# PlantDuino_v2_0.net
KiCad netlist of a schematic drawn in EAGLE
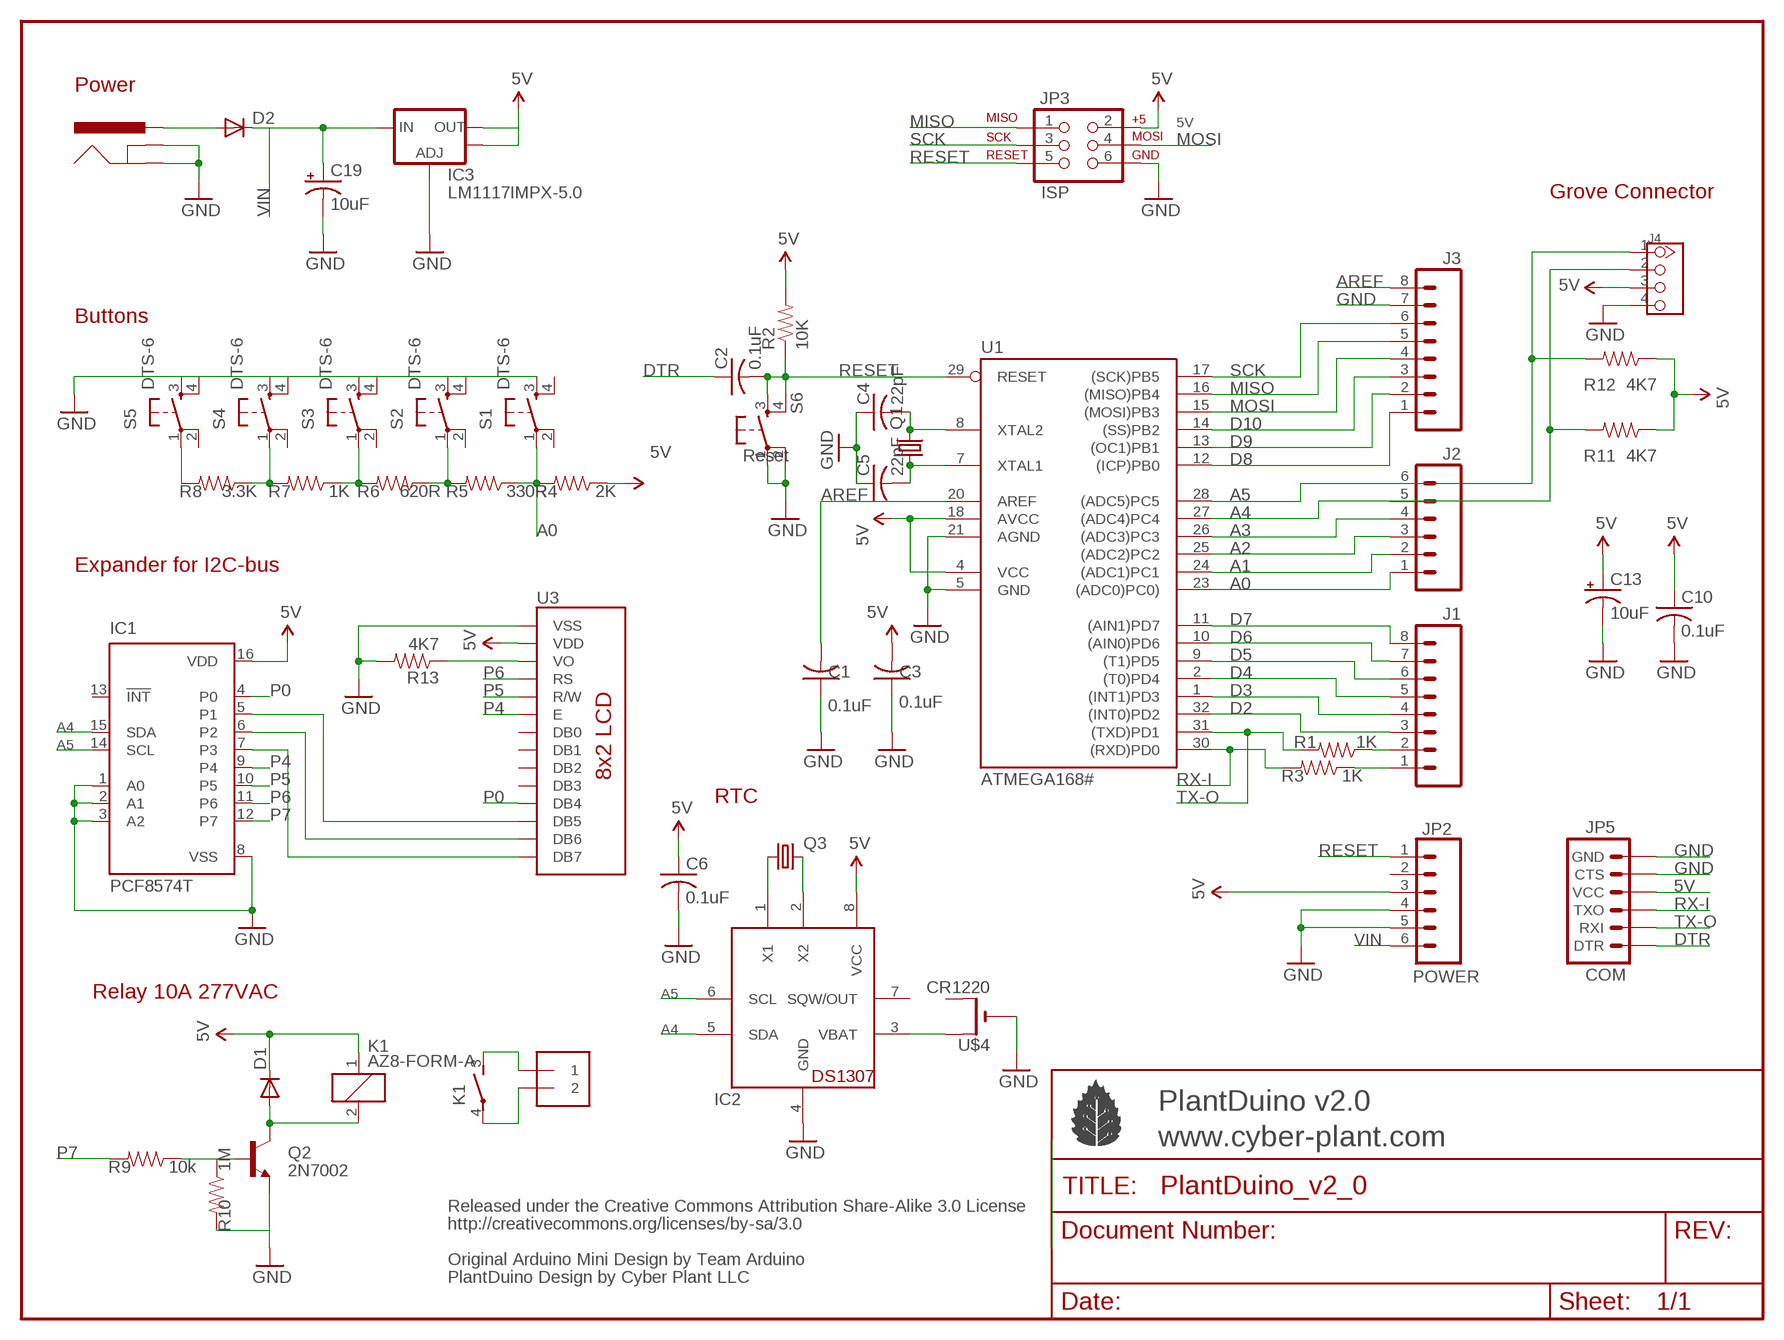
[diagram p0: schematic, sheet 1]

(export (version "E")
  (design (tool "Eeschema 10.0.6"))
  (components
    (comp (ref "C1")
      (value "0.1uF")
      (footprint "eagle-import:C1206")
      (libsource (lib "eagle-import") (part "C-USC1206"))
    )
    (comp (ref "C2")
      (value "0.1uF")
      (footprint "eagle-import:C1206")
      (libsource (lib "eagle-import") (part "C-USC1206"))
    )
    (comp (ref "C3")
      (value "0.1uF")
      (footprint "eagle-import:C1206")
      (libsource (lib "eagle-import") (part "C-USC1206"))
    )
    (comp (ref "C4")
      (value "22pF")
      (footprint "eagle-import:C1206")
      (libsource (lib "eagle-import") (part "C-USC1206"))
    )
    (comp (ref "C5")
      (value "22pF")
      (footprint "eagle-import:C1206")
      (libsource (lib "eagle-import") (part "C-USC1206"))
    )
    (comp (ref "C6")
      (value "0.1uF")
      (footprint "eagle-import:C1206")
      (libsource (lib "eagle-import") (part "C-USC1206"))
    )
    (comp (ref "C10")
      (value "0.1uF")
      (footprint "eagle-import:C1206")
      (libsource (lib "eagle-import") (part "C-USC1206"))
    )
    (comp (ref "C13")
      (value "10uF")
      (footprint "eagle-import:EIA6032")
      (libsource (lib "eagle-import") (part "CAP_POL6032"))
    )
    (comp (ref "C19")
      (value "10uF")
      (footprint "eagle-import:EIA6032")
      (libsource (lib "eagle-import") (part "CAP_POL6032"))
    )
    (comp (ref "D1")
      (value "DIODESMA")
      (footprint "eagle-import:SMA-DIODE")
      (libsource (lib "eagle-import") (part "DIODESMA"))
    )
    (comp (ref "D2")
      (value "DIODESMA")
      (footprint "eagle-import:SMA-DIODE")
      (libsource (lib "eagle-import") (part "DIODESMA"))
    )
    (comp (ref "IC1")
      (value "PCF8574T")
      (footprint "eagle-import:SO16W")
      (fields (field (name "MPN") "PCF8574T/3,512"))
      (libsource (lib "eagle-import") (part "PCF8574T"))
    )
    (comp (ref "IC2")
      (value "DS1307")
      (footprint "eagle-import:SO08")
      (libsource (lib "eagle-import") (part "DS1307"))
    )
    (comp (ref "IC3")
      (value "LM1117IMPX-5.0")
      (footprint "eagle-import:SOT223")
      (libsource (lib "eagle-import") (part "V_REG_LM1117SOT223"))
    )
    (comp (ref "J1")
      (value "M08LONGPADS")
      (footprint "eagle-import:1X08_LONGPADS")
      (libsource (lib "eagle-import") (part "M08LONGPADS"))
    )
    (comp (ref "J2")
      (value "M06LONGPADS")
      (footprint "eagle-import:1X06_LONGPADS")
      (libsource (lib "eagle-import") (part "M06LONGPADS"))
    )
    (comp (ref "J3")
      (value "M08LONGPADS")
      (footprint "eagle-import:1X08_LONGPADS")
      (libsource (lib "eagle-import") (part "M08LONGPADS"))
    )
    (comp (ref "J4")
      (value "TWIG-4P-2.090D")
      (footprint "eagle-import:4P-2.0-90D")
      (libsource (lib "eagle-import") (part "TWIG-4P-2.090D"))
    )
    (comp (ref "JP1")
      (value "1X2-3.5MM")
      (footprint "eagle-import:1X2-3.5MM")
      (libsource (lib "eagle-import") (part "1X2-3.5MM"))
    )
    (comp (ref "JP2")
      (value "POWER")
      (footprint "eagle-import:1X06_LONGPADS")
      (libsource (lib "eagle-import") (part "M06LONGPADS"))
    )
    (comp (ref "JP3")
      (value "ISP")
      (footprint "eagle-import:2X3")
      (libsource (lib "eagle-import") (part "AVR_SPI_PRG_6PTH"))
    )
    (comp (ref "JP4")
      (value "Power Jack")
      (footprint "eagle-import:POWER_JACK_PTH")
      (libsource (lib "eagle-import") (part "POWER_JACKPTH"))
    )
    (comp (ref "JP5")
      (value "COM")
      (footprint "eagle-import:1X06")
      (libsource (lib "eagle-import") (part "ARDUINO_SERIAL_PROGRAMPTH"))
    )
    (comp (ref "K1")
      (value "AZ8-FORM-A")
      (footprint "eagle-import:AZ8")
      (libsource (lib "eagle-import") (part "AZ8-FORM-A"))
    )
    (comp (ref "Q1")
      (value "CRYTALHC49S")
      (footprint "eagle-import:HC49_S@1")
      (libsource (lib "eagle-import") (part "CRYTALHC49S"))
    )
    (comp (ref "Q2")
      (value "2N7002")
      (footprint "eagle-import:SOT23")
      (libsource (lib "eagle-import") (part "TRANSISTOR_NPNSOT23"))
    )
    (comp (ref "Q3")
      (value "CRYSTALTC26H")
      (footprint "eagle-import:TC26H")
      (libsource (lib "eagle-import") (part "CRYSTALTC26H"))
    )
    (comp (ref "R1")
      (value "1K")
      (footprint "eagle-import:1206")
      (libsource (lib "eagle-import") (part "RESISTOR1206"))
    )
    (comp (ref "R2")
      (value "10K")
      (footprint "eagle-import:1206")
      (libsource (lib "eagle-import") (part "RESISTOR1206"))
    )
    (comp (ref "R3")
      (value "1K")
      (footprint "eagle-import:1206")
      (libsource (lib "eagle-import") (part "RESISTOR1206"))
    )
    (comp (ref "R4")
      (value "2K")
      (footprint "eagle-import:1206")
      (libsource (lib "eagle-import") (part "RESISTOR1206"))
    )
    (comp (ref "R5")
      (value "330R")
      (footprint "eagle-import:1206")
      (libsource (lib "eagle-import") (part "RESISTOR1206"))
    )
    (comp (ref "R6")
      (value "620R")
      (footprint "eagle-import:1206")
      (libsource (lib "eagle-import") (part "RESISTOR1206"))
    )
    (comp (ref "R7")
      (value "1K")
      (footprint "eagle-import:1206")
      (libsource (lib "eagle-import") (part "RESISTOR1206"))
    )
    (comp (ref "R8")
      (value "3.3K")
      (footprint "eagle-import:1206")
      (libsource (lib "eagle-import") (part "RESISTOR1206"))
    )
    (comp (ref "R9")
      (value "10k")
      (footprint "eagle-import:1206")
      (libsource (lib "eagle-import") (part "RESISTOR1206"))
    )
    (comp (ref "R10")
      (value "1M")
      (footprint "eagle-import:1206")
      (libsource (lib "eagle-import") (part "RESISTOR1206"))
    )
    (comp (ref "R11")
      (value "4K7")
      (footprint "eagle-import:1206")
      (libsource (lib "eagle-import") (part "RESISTOR1206"))
    )
    (comp (ref "R12")
      (value "4K7")
      (footprint "eagle-import:1206")
      (libsource (lib "eagle-import") (part "RESISTOR1206"))
    )
    (comp (ref "R13")
      (value "4K7")
      (footprint "eagle-import:1206")
      (libsource (lib "eagle-import") (part "RESISTOR1206"))
    )
    (comp (ref "S1")
      (value "DTS-6")
      (footprint "eagle-import:DTS-6")
      (libsource (lib "eagle-import") (part "DTS-6"))
    )
    (comp (ref "S2")
      (value "DTS-6")
      (footprint "eagle-import:DTS-6")
      (libsource (lib "eagle-import") (part "DTS-6"))
    )
    (comp (ref "S3")
      (value "DTS-6")
      (footprint "eagle-import:DTS-6")
      (libsource (lib "eagle-import") (part "DTS-6"))
    )
    (comp (ref "S4")
      (value "DTS-6")
      (footprint "eagle-import:DTS-6")
      (libsource (lib "eagle-import") (part "DTS-6"))
    )
    (comp (ref "S5")
      (value "DTS-6")
      (footprint "eagle-import:DTS-6")
      (libsource (lib "eagle-import") (part "DTS-6"))
    )
    (comp (ref "S6")
      (value "Reset")
      (footprint "eagle-import:DTS-6")
      (libsource (lib "eagle-import") (part "DTS-6"))
    )
    (comp (ref "U$4")
      (value "CR1220")
      (footprint "eagle-import:CR1220-THM")
      (libsource (lib "eagle-import") (part "CR1220THM"))
    )
    (comp (ref "U1")
      (value "ATMEGA168#")
      (footprint "eagle-import:TQFP32-08")
      (libsource (lib "eagle-import") (part "AT90S4433A"))
    )
    (comp (ref "U3")
      (value "LCD-8X2-WH0802A8X2")
      (footprint "eagle-import:LCD-8X2-WH0802A")
      (libsource (lib "eagle-import") (part "LCD-8X2-WH0802A8X2"))
    )
  )
  (nets
    (net (code "1") (name "/A0") (class "Default")
      (node (ref "J2") (pin "1") (pinfunction "1_1") (pintype "passive"))
      (node (ref "R4") (pin "2") (pinfunction "2_2") (pintype "passive"))
      (node (ref "R5") (pin "1") (pinfunction "1_1") (pintype "passive"))
      (node (ref "S1") (pin "1") (pinfunction "1_1") (pintype "passive"))
      (node (ref "U1") (pin "23") (pinfunction "(ADC0)PC0)_23") (pintype "bidirectional"))
    )
    (net (code "2") (name "/A1") (class "Default")
      (node (ref "J2") (pin "2") (pinfunction "2_2") (pintype "passive"))
      (node (ref "U1") (pin "24") (pinfunction "(ADC1)PC1_24") (pintype "bidirectional"))
    )
    (net (code "3") (name "/A2") (class "Default")
      (node (ref "J2") (pin "3") (pinfunction "3_3") (pintype "passive"))
      (node (ref "U1") (pin "25") (pinfunction "(ADC2)PC2_25") (pintype "bidirectional"))
    )
    (net (code "4") (name "/A3") (class "Default")
      (node (ref "J2") (pin "4") (pinfunction "4_4") (pintype "passive"))
      (node (ref "U1") (pin "26") (pinfunction "(ADC3)PC3_26") (pintype "bidirectional"))
    )
    (net (code "5") (name "/A4") (class "Default")
      (node (ref "IC1") (pin "15") (pinfunction "SDA_15") (pintype "bidirectional"))
      (node (ref "IC2") (pin "5") (pinfunction "SDA_5") (pintype "bidirectional"))
      (node (ref "J2") (pin "5") (pinfunction "5_5") (pintype "passive"))
      (node (ref "J4") (pin "2") (pinfunction "2_2") (pintype "bidirectional"))
      (node (ref "R11") (pin "2") (pinfunction "2_2") (pintype "passive"))
      (node (ref "U1") (pin "27") (pinfunction "(ADC4)PC4_27") (pintype "bidirectional"))
    )
    (net (code "6") (name "/A5") (class "Default")
      (node (ref "IC1") (pin "14") (pinfunction "SCL_14") (pintype "input"))
      (node (ref "IC2") (pin "6") (pinfunction "SCL_6") (pintype "bidirectional"))
      (node (ref "J2") (pin "6") (pinfunction "6_6") (pintype "passive"))
      (node (ref "J4") (pin "1") (pinfunction "1_1") (pintype "bidirectional"))
      (node (ref "R12") (pin "2") (pinfunction "2_2") (pintype "passive"))
      (node (ref "U1") (pin "28") (pinfunction "(ADC5)PC5_28") (pintype "bidirectional"))
    )
    (net (code "7") (name "/AREF") (class "Default")
      (node (ref "C1") (pin "2") (pinfunction "2_2") (pintype "passive"))
      (node (ref "J3") (pin "8") (pinfunction "8_8") (pintype "passive"))
      (node (ref "U1") (pin "20") (pinfunction "AREF_20") (pintype "power_in"))
    )
    (net (code "8") (name "/D2") (class "Default")
      (node (ref "J1") (pin "3") (pinfunction "3_3") (pintype "passive"))
      (node (ref "U1") (pin "32") (pinfunction "(INT0)PD2_32") (pintype "bidirectional"))
    )
    (net (code "9") (name "/D3") (class "Default")
      (node (ref "J1") (pin "4") (pinfunction "4_4") (pintype "passive"))
      (node (ref "U1") (pin "1") (pinfunction "(INT1)PD3_1") (pintype "bidirectional"))
    )
    (net (code "10") (name "/D4") (class "Default")
      (node (ref "J1") (pin "5") (pinfunction "5_5") (pintype "passive"))
      (node (ref "U1") (pin "2") (pinfunction "(T0)PD4_2") (pintype "bidirectional"))
    )
    (net (code "11") (name "/D5") (class "Default")
      (node (ref "J1") (pin "6") (pinfunction "6_6") (pintype "passive"))
      (node (ref "U1") (pin "9") (pinfunction "(T1)PD5_9") (pintype "bidirectional"))
    )
    (net (code "12") (name "/D6") (class "Default")
      (node (ref "J1") (pin "7") (pinfunction "7_7") (pintype "passive"))
      (node (ref "U1") (pin "10") (pinfunction "(AIN0)PD6_10") (pintype "bidirectional"))
    )
    (net (code "13") (name "/D7") (class "Default")
      (node (ref "J1") (pin "8") (pinfunction "8_8") (pintype "passive"))
      (node (ref "U1") (pin "11") (pinfunction "(AIN1)PD7_11") (pintype "bidirectional"))
    )
    (net (code "14") (name "/D8") (class "Default")
      (node (ref "J3") (pin "1") (pinfunction "1_1") (pintype "passive"))
      (node (ref "U1") (pin "12") (pinfunction "(ICP)PB0_12") (pintype "bidirectional"))
    )
    (net (code "15") (name "/D9") (class "Default")
      (node (ref "J3") (pin "2") (pinfunction "2_2") (pintype "passive"))
      (node (ref "U1") (pin "13") (pinfunction "(OC1)PB1_13") (pintype "bidirectional"))
    )
    (net (code "16") (name "/D10") (class "Default")
      (node (ref "J3") (pin "3") (pinfunction "3_3") (pintype "passive"))
      (node (ref "U1") (pin "14") (pinfunction "(SS)PB2_14") (pintype "bidirectional"))
    )
    (net (code "17") (name "/DTR") (class "Default")
      (node (ref "C2") (pin "1") (pinfunction "1_1") (pintype "passive"))
      (node (ref "JP5") (pin "1") (pinfunction "DTR_1") (pintype "passive"))
    )
    (net (code "18") (name "/MISO") (class "Default")
      (node (ref "J3") (pin "5") (pinfunction "5_5") (pintype "passive"))
      (node (ref "JP3") (pin "1") (pinfunction "1_1") (pintype "passive"))
      (node (ref "U1") (pin "16") (pinfunction "(MISO)PB4_16") (pintype "bidirectional"))
    )
    (net (code "19") (name "/MOSI") (class "Default")
      (node (ref "J3") (pin "4") (pinfunction "4_4") (pintype "passive"))
      (node (ref "JP3") (pin "4") (pinfunction "4_4") (pintype "passive"))
      (node (ref "U1") (pin "15") (pinfunction "(MOSI)PB3_15") (pintype "bidirectional"))
    )
    (net (code "20") (name "/P0") (class "Default")
      (node (ref "IC1") (pin "4") (pinfunction "P0_4") (pintype "bidirectional"))
      (node (ref "U3") (pin "11") (pinfunction "DB4_11") (pintype "bidirectional"))
    )
    (net (code "21") (name "/P4") (class "Default")
      (node (ref "IC1") (pin "9") (pinfunction "P4_9") (pintype "bidirectional"))
      (node (ref "U3") (pin "6") (pinfunction "E_6") (pintype "input"))
    )
    (net (code "22") (name "/P5") (class "Default")
      (node (ref "IC1") (pin "10") (pinfunction "P5_10") (pintype "bidirectional"))
      (node (ref "U3") (pin "5") (pinfunction "R/W_5") (pintype "input"))
    )
    (net (code "23") (name "/P6") (class "Default")
      (node (ref "IC1") (pin "11") (pinfunction "P6_11") (pintype "bidirectional"))
      (node (ref "U3") (pin "4") (pinfunction "RS_4") (pintype "input"))
    )
    (net (code "24") (name "/P7") (class "Default")
      (node (ref "IC1") (pin "12") (pinfunction "P7_12") (pintype "bidirectional"))
      (node (ref "R9") (pin "2") (pinfunction "2_2") (pintype "passive"))
    )
    (net (code "25") (name "/RESET") (class "Default")
      (node (ref "C2") (pin "2") (pinfunction "2_2") (pintype "passive"))
      (node (ref "JP2") (pin "1") (pinfunction "1_1") (pintype "passive"))
      (node (ref "JP3") (pin "5") (pinfunction "5_5") (pintype "passive"))
      (node (ref "R2") (pin "1") (pinfunction "1_1") (pintype "passive"))
      (node (ref "S6") (pin "3") (pinfunction "3_3") (pintype "passive"))
      (node (ref "S6") (pin "4") (pinfunction "4_4") (pintype "passive"))
      (node (ref "U1") (pin "29") (pinfunction "RESET_29") (pintype "input"))
    )
    (net (code "26") (name "/RX-I") (class "Default")
      (node (ref "JP5") (pin "3") (pinfunction "TXO_3") (pintype "passive"))
      (node (ref "R3") (pin "2") (pinfunction "2_2") (pintype "passive"))
      (node (ref "U1") (pin "30") (pinfunction "(RXD)PD0_30") (pintype "bidirectional"))
    )
    (net (code "27") (name "/SCK") (class "Default")
      (node (ref "J3") (pin "6") (pinfunction "6_6") (pintype "passive"))
      (node (ref "JP3") (pin "3") (pinfunction "3_3") (pintype "passive"))
      (node (ref "U1") (pin "17") (pinfunction "(SCK)PB5_17") (pintype "bidirectional"))
    )
    (net (code "28") (name "/TX-O") (class "Default")
      (node (ref "JP5") (pin "2") (pinfunction "RXI_2") (pintype "passive"))
      (node (ref "R1") (pin "2") (pinfunction "2_2") (pintype "passive"))
      (node (ref "U1") (pin "31") (pinfunction "(TXD)PD1_31") (pintype "bidirectional"))
    )
    (net (code "29") (name "/VIN") (class "Default")
      (node (ref "C19") (pin "P$1") (pinfunction "+_P$1") (pintype "passive"))
      (node (ref "D2") (pin "C") (pinfunction "C_C") (pintype "passive"))
      (node (ref "IC3") (pin "3") (pinfunction "IN_3") (pintype "input"))
      (node (ref "JP2") (pin "6") (pinfunction "6_6") (pintype "passive"))
    )
    (net (code "30") (name "5V") (class "Default")
      (node (ref "C10") (pin "1") (pinfunction "1_1") (pintype "passive"))
      (node (ref "C13") (pin "P$1") (pinfunction "+_P$1") (pintype "passive"))
      (node (ref "C3") (pin "2") (pinfunction "2_2") (pintype "passive"))
      (node (ref "C6") (pin "1") (pinfunction "1_1") (pintype "passive"))
      (node (ref "D1") (pin "C") (pinfunction "C_C") (pintype "passive"))
      (node (ref "IC1") (pin "16") (pinfunction "VDD_16") (pintype "power_in"))
      (node (ref "IC2") (pin "8") (pinfunction "VCC_8") (pintype "power_in"))
      (node (ref "IC3") (pin "2") (pinfunction "OUT_2") (pintype "output"))
      (node (ref "IC3") (pin "4") (pinfunction "OUT_4") (pintype "output"))
      (node (ref "J4") (pin "3") (pinfunction "3_3") (pintype "bidirectional"))
      (node (ref "JP2") (pin "3") (pinfunction "3_3") (pintype "passive"))
      (node (ref "JP3") (pin "2") (pinfunction "2_2") (pintype "passive"))
      (node (ref "JP5") (pin "4") (pinfunction "VCC_4") (pintype "passive"))
      (node (ref "K1") (pin "1") (pinfunction "1_1") (pintype "passive"))
      (node (ref "R11") (pin "1") (pinfunction "1_1") (pintype "passive"))
      (node (ref "R12") (pin "1") (pinfunction "1_1") (pintype "passive"))
      (node (ref "R2") (pin "2") (pinfunction "2_2") (pintype "passive"))
      (node (ref "R4") (pin "1") (pinfunction "1_1") (pintype "passive"))
      (node (ref "U1") (pin "18") (pinfunction "AVCC_18") (pintype "power_in"))
      (node (ref "U1") (pin "4") (pinfunction "VCC_4") (pintype "power_in"))
      (node (ref "U3") (pin "2") (pinfunction "VDD_2") (pintype "power_in"))
    )
    (net (code "31") (name "GND") (class "Default")
      (node (ref "C1") (pin "1") (pinfunction "1_1") (pintype "passive"))
      (node (ref "C10") (pin "2") (pinfunction "2_2") (pintype "passive"))
      (node (ref "C13") (pin "P$2") (pinfunction "-_P$2") (pintype "passive"))
      (node (ref "C19") (pin "P$2") (pinfunction "-_P$2") (pintype "passive"))
      (node (ref "C3") (pin "1") (pinfunction "1_1") (pintype "passive"))
      (node (ref "C4") (pin "1") (pinfunction "1_1") (pintype "passive"))
      (node (ref "C5") (pin "1") (pinfunction "1_1") (pintype "passive"))
      (node (ref "C6") (pin "2") (pinfunction "2_2") (pintype "passive"))
      (node (ref "IC1") (pin "1") (pinfunction "A0_1") (pintype "input"))
      (node (ref "IC1") (pin "2") (pinfunction "A1_2") (pintype "input"))
      (node (ref "IC1") (pin "3") (pinfunction "A2_3") (pintype "input"))
      (node (ref "IC1") (pin "8") (pinfunction "VSS_8") (pintype "power_in"))
      (node (ref "IC2") (pin "4") (pinfunction "GND_4") (pintype "power_in"))
      (node (ref "IC3") (pin "1") (pinfunction "ADJ_1") (pintype "input"))
      (node (ref "J3") (pin "7") (pinfunction "7_7") (pintype "passive"))
      (node (ref "J4") (pin "4") (pinfunction "4_4") (pintype "bidirectional"))
      (node (ref "JP2") (pin "4") (pinfunction "4_4") (pintype "passive"))
      (node (ref "JP2") (pin "5") (pinfunction "5_5") (pintype "passive"))
      (node (ref "JP3") (pin "6") (pinfunction "6_6") (pintype "passive"))
      (node (ref "JP4") (pin "GND") (pinfunction "GND_GND") (pintype "bidirectional"))
      (node (ref "JP4") (pin "GNDBREAK") (pinfunction "GNDBREAK_GNDBREAK") (pintype "bidirectional"))
      (node (ref "JP5") (pin "5") (pinfunction "CTS_5") (pintype "passive"))
      (node (ref "JP5") (pin "6") (pinfunction "GND_6") (pintype "passive"))
      (node (ref "Q2") (pin "2") (pinfunction "E_2") (pintype "passive"))
      (node (ref "R10") (pin "2") (pinfunction "2_2") (pintype "passive"))
      (node (ref "R13") (pin "2") (pinfunction "2_2") (pintype "passive"))
      (node (ref "S1") (pin "3") (pinfunction "3_3") (pintype "passive"))
      (node (ref "S2") (pin "3") (pinfunction "3_3") (pintype "passive"))
      (node (ref "S2") (pin "4") (pinfunction "4_4") (pintype "passive"))
      (node (ref "S3") (pin "3") (pinfunction "3_3") (pintype "passive"))
      (node (ref "S3") (pin "4") (pinfunction "4_4") (pintype "passive"))
      (node (ref "S4") (pin "3") (pinfunction "3_3") (pintype "passive"))
      (node (ref "S4") (pin "4") (pinfunction "4_4") (pintype "passive"))
      (node (ref "S5") (pin "3") (pinfunction "3_3") (pintype "passive"))
      (node (ref "S5") (pin "4") (pinfunction "4_4") (pintype "passive"))
      (node (ref "S6") (pin "1") (pinfunction "1_1") (pintype "passive"))
      (node (ref "S6") (pin "2") (pinfunction "2_2") (pintype "passive"))
      (node (ref "U$4") (pin "-") (pinfunction "-_-") (pintype "passive"))
      (node (ref "U1") (pin "21") (pinfunction "AGND_21") (pintype "power_in"))
      (node (ref "U1") (pin "5") (pinfunction "GND_5") (pintype "power_in"))
      (node (ref "U3") (pin "1") (pinfunction "VSS_1") (pintype "power_in"))
    )
    (net (code "32") (name "Net-(D2-PadA)") (class "Default")
      (node (ref "D2") (pin "A") (pinfunction "A_A") (pintype "passive"))
      (node (ref "JP4") (pin "PWR") (pinfunction "PWR_PWR") (pintype "bidirectional"))
    )
    (net (code "33") (name "Net-(IC1-P1)") (class "Default")
      (node (ref "IC1") (pin "5") (pinfunction "P1_5") (pintype "bidirectional"))
      (node (ref "U3") (pin "12") (pinfunction "DB5_12") (pintype "bidirectional"))
    )
    (net (code "34") (name "Net-(IC1-P2)") (class "Default")
      (node (ref "IC1") (pin "6") (pinfunction "P2_6") (pintype "bidirectional"))
      (node (ref "U3") (pin "13") (pinfunction "DB6_13") (pintype "bidirectional"))
    )
    (net (code "35") (name "Net-(IC1-P3)") (class "Default")
      (node (ref "IC1") (pin "7") (pinfunction "P3_7") (pintype "bidirectional"))
      (node (ref "U3") (pin "14") (pinfunction "DB7_14") (pintype "bidirectional"))
    )
    (net (code "36") (name "Net-(IC2-VBAT)") (class "Default")
      (node (ref "IC2") (pin "3") (pinfunction "VBAT_3") (pintype "power_in"))
      (node (ref "U$4") (pin "+1") (pinfunction "+_+1") (pintype "passive"))
    )
    (net (code "37") (name "Net-(IC2-X1)") (class "Default")
      (node (ref "IC2") (pin "1") (pinfunction "X1_1") (pintype "passive"))
      (node (ref "Q3") (pin "1") (pinfunction "1_1") (pintype "passive"))
    )
    (net (code "38") (name "Net-(IC2-X2)") (class "Default")
      (node (ref "IC2") (pin "2") (pinfunction "X2_2") (pintype "passive"))
      (node (ref "Q3") (pin "2") (pinfunction "2_2") (pintype "passive"))
    )
    (net (code "39") (name "Net-(J1-Pad1)") (class "Default")
      (node (ref "J1") (pin "1") (pinfunction "1_1") (pintype "passive"))
      (node (ref "R3") (pin "1") (pinfunction "1_1") (pintype "passive"))
    )
    (net (code "40") (name "Net-(J1-Pad2)") (class "Default")
      (node (ref "J1") (pin "2") (pinfunction "2_2") (pintype "passive"))
      (node (ref "R1") (pin "1") (pinfunction "1_1") (pintype "passive"))
    )
    (net (code "41") (name "Net-(K1A-P)") (class "Default")
      (node (ref "JP1") (pin "2") (pinfunction "2_2") (pintype "passive"))
      (node (ref "K1") (pin "4") (pinfunction "P_4") (pintype "passive"))
    )
    (net (code "42") (name "Net-(K1A-S)") (class "Default")
      (node (ref "JP1") (pin "1") (pinfunction "1_1") (pintype "passive"))
      (node (ref "K1") (pin "3") (pinfunction "S_3") (pintype "passive"))
    )
    (net (code "43") (name "Net-(Q2-B)") (class "Default")
      (node (ref "Q2") (pin "1") (pinfunction "B_1") (pintype "passive"))
      (node (ref "R10") (pin "1") (pinfunction "1_1") (pintype "passive"))
      (node (ref "R9") (pin "1") (pinfunction "1_1") (pintype "passive"))
    )
    (net (code "44") (name "Net-(Q2-C)") (class "Default")
      (node (ref "D1") (pin "A") (pinfunction "A_A") (pintype "passive"))
      (node (ref "K1") (pin "2") (pinfunction "2_2") (pintype "passive"))
      (node (ref "Q2") (pin "3") (pinfunction "C_3") (pintype "passive"))
    )
    (net (code "45") (name "Net-(R5-Pad2)") (class "Default")
      (node (ref "R5") (pin "2") (pinfunction "2_2") (pintype "passive"))
      (node (ref "R6") (pin "1") (pinfunction "1_1") (pintype "passive"))
      (node (ref "S2") (pin "1") (pinfunction "1_1") (pintype "passive"))
    )
    (net (code "46") (name "Net-(R6-Pad2)") (class "Default")
      (node (ref "R6") (pin "2") (pinfunction "2_2") (pintype "passive"))
      (node (ref "R7") (pin "1") (pinfunction "1_1") (pintype "passive"))
      (node (ref "S3") (pin "1") (pinfunction "1_1") (pintype "passive"))
    )
    (net (code "47") (name "Net-(R7-Pad2)") (class "Default")
      (node (ref "R7") (pin "2") (pinfunction "2_2") (pintype "passive"))
      (node (ref "R8") (pin "1") (pinfunction "1_1") (pintype "passive"))
      (node (ref "S4") (pin "1") (pinfunction "1_1") (pintype "passive"))
    )
    (net (code "48") (name "Net-(R8-Pad2)") (class "Default")
      (node (ref "R8") (pin "2") (pinfunction "2_2") (pintype "passive"))
      (node (ref "S5") (pin "1") (pinfunction "1_1") (pintype "passive"))
    )
    (net (code "49") (name "Net-(U1-XTAL1)") (class "Default")
      (node (ref "C5") (pin "2") (pinfunction "2_2") (pintype "passive"))
      (node (ref "Q1") (pin "1") (pinfunction "1_1") (pintype "passive"))
      (node (ref "U1") (pin "7") (pinfunction "XTAL1_7") (pintype "bidirectional"))
    )
    (net (code "50") (name "Net-(U1-XTAL2)") (class "Default")
      (node (ref "C4") (pin "2") (pinfunction "2_2") (pintype "passive"))
      (node (ref "Q1") (pin "2") (pinfunction "2_2") (pintype "passive"))
      (node (ref "U1") (pin "8") (pinfunction "XTAL2_8") (pintype "bidirectional"))
    )
    (net (code "51") (name "Net-(U3-VO)") (class "Default")
      (node (ref "R13") (pin "1") (pinfunction "1_1") (pintype "passive"))
      (node (ref "U3") (pin "3") (pinfunction "VO_3") (pintype "bidirectional"))
    )
    (net (code "52") (name "unconnected-(IC1-~{INT}-Pad13)") (class "Default")
      (node (ref "IC1") (pin "13") (pinfunction "~{INT}_13") (pintype "output"))
    )
    (net (code "53") (name "unconnected-(IC2-SQW{slash}OUT-Pad7)") (class "Default")
      (node (ref "IC2") (pin "7") (pinfunction "SQW/OUT_7") (pintype "bidirectional"))
    )
    (net (code "54") (name "unconnected-(JP2-Pad2)") (class "Default")
      (node (ref "JP2") (pin "2") (pinfunction "2_2") (pintype "passive"))
    )
    (net (code "55") (name "unconnected-(S1-Pad2)") (class "Default")
      (node (ref "S1") (pin "2") (pinfunction "2_2") (pintype "passive"))
    )
    (net (code "56") (name "unconnected-(S1-Pad4)") (class "Default")
      (node (ref "S1") (pin "4") (pinfunction "4_4") (pintype "passive"))
    )
    (net (code "57") (name "unconnected-(S2-Pad2)") (class "Default")
      (node (ref "S2") (pin "2") (pinfunction "2_2") (pintype "passive"))
    )
    (net (code "58") (name "unconnected-(S3-Pad2)") (class "Default")
      (node (ref "S3") (pin "2") (pinfunction "2_2") (pintype "passive"))
    )
    (net (code "59") (name "unconnected-(S4-Pad2)") (class "Default")
      (node (ref "S4") (pin "2") (pinfunction "2_2") (pintype "passive"))
    )
    (net (code "60") (name "unconnected-(S5-Pad2)") (class "Default")
      (node (ref "S5") (pin "2") (pinfunction "2_2") (pintype "passive"))
    )
    (net (code "61") (name "unconnected-(U$4-+1-Pad+2)") (class "Default")
      (node (ref "U$4") (pin "+2") (pinfunction "+1_+2") (pintype "passive"))
    )
    (net (code "62") (name "unconnected-(U3-DB0-Pad7)") (class "Default")
      (node (ref "U3") (pin "7") (pinfunction "DB0_7") (pintype "bidirectional"))
    )
    (net (code "63") (name "unconnected-(U3-DB1-Pad8)") (class "Default")
      (node (ref "U3") (pin "8") (pinfunction "DB1_8") (pintype "bidirectional"))
    )
    (net (code "64") (name "unconnected-(U3-DB2-Pad9)") (class "Default")
      (node (ref "U3") (pin "9") (pinfunction "DB2_9") (pintype "bidirectional"))
    )
    (net (code "65") (name "unconnected-(U3-DB3-Pad10)") (class "Default")
      (node (ref "U3") (pin "10") (pinfunction "DB3_10") (pintype "bidirectional"))
    )
  )
)
